# Versie_3.net
KiCad netlist of a schematic drawn in EAGLE
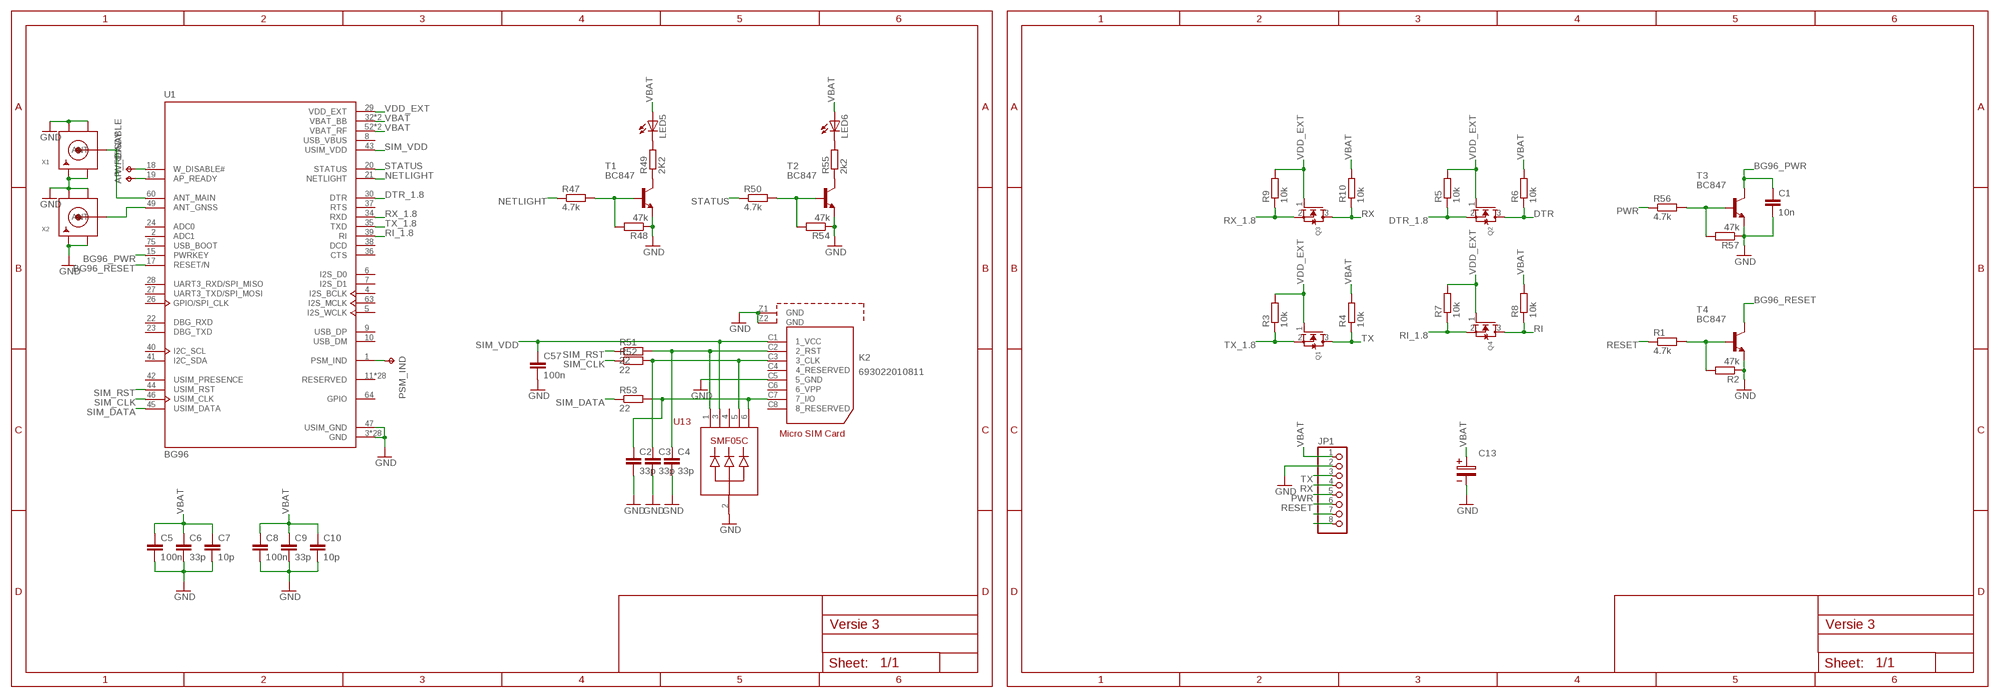
[diagram p0: schematic, sheet 1]

(export (version "E")
  (design (tool "Eeschema 10.0.6"))
  (components
    (comp (ref "AP_READY")
      (value "TPTP10R")
      (footprint "eagle-import:TP10R")
      (libsource (lib "eagle-import") (part "TPTP10R"))
    )
    (comp (ref "C1")
      (value "10n")
      (footprint "eagle-import:C0603")
      (libsource (lib "eagle-import") (part "C-EUC0603"))
    )
    (comp (ref "C2")
      (value "33p")
      (footprint "eagle-import:C0603")
      (libsource (lib "eagle-import") (part "C-EUC0603"))
    )
    (comp (ref "C3")
      (value "33p")
      (footprint "eagle-import:C0603")
      (libsource (lib "eagle-import") (part "C-EUC0603"))
    )
    (comp (ref "C4")
      (value "33p")
      (footprint "eagle-import:C0603")
      (libsource (lib "eagle-import") (part "C-EUC0603"))
    )
    (comp (ref "C5")
      (value "100n")
      (footprint "eagle-import:C0603")
      (libsource (lib "eagle-import") (part "C-EUC0603"))
    )
    (comp (ref "C6")
      (value "33p")
      (footprint "eagle-import:C0603")
      (libsource (lib "eagle-import") (part "C-EUC0603"))
    )
    (comp (ref "C7")
      (value "10p")
      (footprint "eagle-import:C0603")
      (libsource (lib "eagle-import") (part "C-EUC0603"))
    )
    (comp (ref "C8")
      (value "100n")
      (footprint "eagle-import:C0603")
      (libsource (lib "eagle-import") (part "C-EUC0603"))
    )
    (comp (ref "C9")
      (value "33p")
      (footprint "eagle-import:C0603")
      (libsource (lib "eagle-import") (part "C-EUC0603"))
    )
    (comp (ref "C10")
      (value "10p")
      (footprint "eagle-import:C0603")
      (libsource (lib "eagle-import") (part "C-EUC0603"))
    )
    (comp (ref "C13")
      (value "WCAP-ASLI_6,3X7,7_865080545012")
      (footprint "eagle-import:3.5X1.6X2.1(BXCXA)")
      (libsource (lib "eagle-import") (part "WCAP-ASLI_865080545012_6,3X7,7"))
    )
    (comp (ref "C57")
      (value "100n")
      (footprint "eagle-import:C0603")
      (libsource (lib "eagle-import") (part "C-EUC0603"))
    )
    (comp (ref "JP1")
      (value "PINHD-1X8")
      (footprint "eagle-import:1X08")
      (libsource (lib "eagle-import") (part "PINHD-1X8"))
    )
    (comp (ref "K2")
      (value "693022010811")
      (footprint "eagle-import:693022010811")
      (libsource (lib "eagle-import") (part "693022010811"))
    )
    (comp (ref "LED5")
      (value "LEDCHIPLED_0805")
      (footprint "eagle-import:CHIPLED_0805")
      (libsource (lib "eagle-import") (part "LEDCHIPLED_0805"))
    )
    (comp (ref "LED6")
      (value "LEDCHIPLED_0805")
      (footprint "eagle-import:CHIPLED_0805")
      (libsource (lib "eagle-import") (part "LEDCHIPLED_0805"))
    )
    (comp (ref "PSM_IND")
      (value "TPTP10R")
      (footprint "eagle-import:TP10R")
      (libsource (lib "eagle-import") (part "TPTP10R"))
    )
    (comp (ref "Q1")
      (value "MOSFET-NREFLOW")
      (footprint "eagle-import:SOT23")
      (libsource (lib "eagle-import") (part "MOSFET-NREFLOW"))
    )
    (comp (ref "Q2")
      (value "MOSFET-NREFLOW")
      (footprint "eagle-import:SOT23")
      (libsource (lib "eagle-import") (part "MOSFET-NREFLOW"))
    )
    (comp (ref "Q3")
      (value "MOSFET-NREFLOW")
      (footprint "eagle-import:SOT23")
      (libsource (lib "eagle-import") (part "MOSFET-NREFLOW"))
    )
    (comp (ref "Q4")
      (value "MOSFET-NREFLOW")
      (footprint "eagle-import:SOT23")
      (libsource (lib "eagle-import") (part "MOSFET-NREFLOW"))
    )
    (comp (ref "R1")
      (value "4.7k")
      (footprint "eagle-import:R0603")
      (libsource (lib "eagle-import") (part "R-EU_R0603"))
    )
    (comp (ref "R2")
      (value "47k")
      (footprint "eagle-import:R0603")
      (libsource (lib "eagle-import") (part "R-EU_R0603"))
    )
    (comp (ref "R3")
      (value "10k")
      (footprint "eagle-import:R0603")
      (libsource (lib "eagle-import") (part "R-EU_R0603"))
    )
    (comp (ref "R4")
      (value "10k")
      (footprint "eagle-import:R0603")
      (libsource (lib "eagle-import") (part "R-EU_R0603"))
    )
    (comp (ref "R5")
      (value "10k")
      (footprint "eagle-import:R0603")
      (libsource (lib "eagle-import") (part "R-EU_R0603"))
    )
    (comp (ref "R6")
      (value "10k")
      (footprint "eagle-import:R0603")
      (libsource (lib "eagle-import") (part "R-EU_R0603"))
    )
    (comp (ref "R7")
      (value "10k")
      (footprint "eagle-import:R0603")
      (libsource (lib "eagle-import") (part "R-EU_R0603"))
    )
    (comp (ref "R8")
      (value "10k")
      (footprint "eagle-import:R0603")
      (libsource (lib "eagle-import") (part "R-EU_R0603"))
    )
    (comp (ref "R9")
      (value "10k")
      (footprint "eagle-import:R0603")
      (libsource (lib "eagle-import") (part "R-EU_R0603"))
    )
    (comp (ref "R10")
      (value "10k")
      (footprint "eagle-import:R0603")
      (libsource (lib "eagle-import") (part "R-EU_R0603"))
    )
    (comp (ref "R47")
      (value "4.7k")
      (footprint "eagle-import:R0603")
      (libsource (lib "eagle-import") (part "R-EU_R0603"))
    )
    (comp (ref "R48")
      (value "47k")
      (footprint "eagle-import:R0603")
      (libsource (lib "eagle-import") (part "R-EU_R0603"))
    )
    (comp (ref "R49")
      (value "2K2")
      (footprint "eagle-import:R0603")
      (libsource (lib "eagle-import") (part "R-EU_R0603"))
    )
    (comp (ref "R50")
      (value "4.7k")
      (footprint "eagle-import:R0603")
      (libsource (lib "eagle-import") (part "R-EU_R0603"))
    )
    (comp (ref "R51")
      (value "22")
      (footprint "eagle-import:R0603")
      (libsource (lib "eagle-import") (part "R-EU_R0603"))
    )
    (comp (ref "R52")
      (value "22")
      (footprint "eagle-import:R0603")
      (libsource (lib "eagle-import") (part "R-EU_R0603"))
    )
    (comp (ref "R53")
      (value "22")
      (footprint "eagle-import:R0603")
      (libsource (lib "eagle-import") (part "R-EU_R0603"))
    )
    (comp (ref "R54")
      (value "47k")
      (footprint "eagle-import:R0603")
      (libsource (lib "eagle-import") (part "R-EU_R0603"))
    )
    (comp (ref "R55")
      (value "2k2")
      (footprint "eagle-import:R0603")
      (libsource (lib "eagle-import") (part "R-EU_R0603"))
    )
    (comp (ref "R56")
      (value "4.7k")
      (footprint "eagle-import:R0603")
      (libsource (lib "eagle-import") (part "R-EU_R0603"))
    )
    (comp (ref "R57")
      (value "47k")
      (footprint "eagle-import:R0603")
      (libsource (lib "eagle-import") (part "R-EU_R0603"))
    )
    (comp (ref "T1")
      (value "BC847")
      (footprint "eagle-import:SOT23")
      (libsource (lib "eagle-import") (part "BC847"))
    )
    (comp (ref "T2")
      (value "BC847")
      (footprint "eagle-import:SOT23")
      (libsource (lib "eagle-import") (part "BC847"))
    )
    (comp (ref "T3")
      (value "BC847")
      (footprint "eagle-import:SOT23")
      (libsource (lib "eagle-import") (part "BC847"))
    )
    (comp (ref "T4")
      (value "BC847")
      (footprint "eagle-import:SOT23")
      (libsource (lib "eagle-import") (part "BC847"))
    )
    (comp (ref "U1")
      (value "BG96")
      (footprint "eagle-import:LTE_MODULE_BG96")
      (fields (field (name "MF") "Quectel"))
      (libsource (lib "eagle-import") (part "BG96"))
    )
    (comp (ref "U13")
      (value "SMF05C")
      (footprint "eagle-import:SC-70-6")
      (libsource (lib "eagle-import") (part "SMF05C"))
    )
    (comp (ref "W_DISABLE")
      (value "TPTP10R")
      (footprint "eagle-import:TP10R")
      (libsource (lib "eagle-import") (part "TPTP10R"))
    )
    (comp (ref "X1")
      (value "SMACONNECTOR_EDGE_UFL")
      (footprint "eagle-import:SMA_EDGELAUNCH_UFL")
      (libsource (lib "eagle-import") (part "SMACONNECTOR_EDGE_UFL"))
    )
    (comp (ref "X2")
      (value "SMACONNECTOR_EDGE_UFL")
      (footprint "eagle-import:SMA_EDGELAUNCH_UFL")
      (libsource (lib "eagle-import") (part "SMACONNECTOR_EDGE_UFL"))
    )
  )
  (nets
    (net (code "1") (name "/BG96_PWR") (class "Default")
      (node (ref "C1") (pin "1") (pinfunction "1_1") (pintype "passive"))
      (node (ref "T3") (pin "3") (pinfunction "C_3") (pintype "passive"))
      (node (ref "U1") (pin "15") (pinfunction "PWRKEY_15") (pintype "input"))
    )
    (net (code "2") (name "/BG96_RESET") (class "Default")
      (node (ref "T4") (pin "3") (pinfunction "C_3") (pintype "passive"))
      (node (ref "U1") (pin "17") (pinfunction "RESET/N_17") (pintype "input"))
    )
    (net (code "3") (name "/DTR") (class "Default")
      (node (ref "JP1") (pin "7") (pinfunction "7_7") (pintype "passive"))
      (node (ref "Q2") (pin "3") (pinfunction "D_3") (pintype "bidirectional"))
      (node (ref "R6") (pin "1") (pinfunction "1_1") (pintype "passive"))
    )
    (net (code "4") (name "/DTR_1.8") (class "Default")
      (node (ref "Q2") (pin "2") (pinfunction "S_2") (pintype "bidirectional"))
      (node (ref "R5") (pin "1") (pinfunction "1_1") (pintype "passive"))
      (node (ref "U1") (pin "30") (pinfunction "DTR_30") (pintype "input"))
    )
    (net (code "5") (name "/NETLIGHT") (class "Default")
      (node (ref "R47") (pin "1") (pinfunction "1_1") (pintype "passive"))
      (node (ref "U1") (pin "21") (pinfunction "NETLIGHT_21") (pintype "output"))
    )
    (net (code "6") (name "/PWR") (class "Default")
      (node (ref "JP1") (pin "5") (pinfunction "5_5") (pintype "passive"))
      (node (ref "R56") (pin "1") (pinfunction "1_1") (pintype "passive"))
    )
    (net (code "7") (name "/RESET") (class "Default")
      (node (ref "JP1") (pin "6") (pinfunction "6_6") (pintype "passive"))
      (node (ref "R1") (pin "1") (pinfunction "1_1") (pintype "passive"))
    )
    (net (code "8") (name "/RI") (class "Default")
      (node (ref "JP1") (pin "8") (pinfunction "8_8") (pintype "passive"))
      (node (ref "Q4") (pin "3") (pinfunction "D_3") (pintype "bidirectional"))
      (node (ref "R8") (pin "1") (pinfunction "1_1") (pintype "passive"))
    )
    (net (code "9") (name "/RI_1.8") (class "Default")
      (node (ref "Q4") (pin "2") (pinfunction "S_2") (pintype "bidirectional"))
      (node (ref "R7") (pin "1") (pinfunction "1_1") (pintype "passive"))
      (node (ref "U1") (pin "39") (pinfunction "RI_39") (pintype "output"))
    )
    (net (code "10") (name "/RX") (class "Default")
      (node (ref "JP1") (pin "4") (pinfunction "4_4") (pintype "passive"))
      (node (ref "Q3") (pin "3") (pinfunction "D_3") (pintype "bidirectional"))
      (node (ref "R10") (pin "1") (pinfunction "1_1") (pintype "passive"))
    )
    (net (code "11") (name "/RX_1.8") (class "Default")
      (node (ref "Q3") (pin "2") (pinfunction "S_2") (pintype "bidirectional"))
      (node (ref "R9") (pin "1") (pinfunction "1_1") (pintype "passive"))
      (node (ref "U1") (pin "34") (pinfunction "RXD_34") (pintype "input"))
    )
    (net (code "12") (name "/SIM_CLK") (class "Default")
      (node (ref "R52") (pin "1") (pinfunction "1_1") (pintype "passive"))
      (node (ref "U1") (pin "46") (pinfunction "USIM_CLK_46") (pintype "output"))
    )
    (net (code "13") (name "/SIM_DATA") (class "Default")
      (node (ref "R53") (pin "1") (pinfunction "1_1") (pintype "passive"))
      (node (ref "U1") (pin "45") (pinfunction "USIM_DATA_45") (pintype "bidirectional"))
    )
    (net (code "14") (name "/SIM_RST") (class "Default")
      (node (ref "R51") (pin "1") (pinfunction "1_1") (pintype "passive"))
      (node (ref "U1") (pin "44") (pinfunction "USIM_RST_44") (pintype "output"))
    )
    (net (code "15") (name "/SIM_VDD") (class "Default")
      (node (ref "C57") (pin "1") (pinfunction "1_1") (pintype "passive"))
      (node (ref "K2") (pin "C1") (pinfunction "1_VCC_C1") (pintype "bidirectional"))
      (node (ref "U1") (pin "43") (pinfunction "USIM_VDD_43") (pintype "power_in"))
      (node (ref "U13") (pin "3") (pinfunction "3_3") (pintype "bidirectional"))
    )
    (net (code "16") (name "/STATUS") (class "Default")
      (node (ref "R50") (pin "1") (pinfunction "1_1") (pintype "passive"))
      (node (ref "U1") (pin "20") (pinfunction "STATUS_20") (pintype "output"))
    )
    (net (code "17") (name "/TX") (class "Default")
      (node (ref "JP1") (pin "3") (pinfunction "3_3") (pintype "passive"))
      (node (ref "Q1") (pin "3") (pinfunction "D_3") (pintype "bidirectional"))
      (node (ref "R4") (pin "1") (pinfunction "1_1") (pintype "passive"))
    )
    (net (code "18") (name "/TX_1.8") (class "Default")
      (node (ref "Q1") (pin "2") (pinfunction "S_2") (pintype "bidirectional"))
      (node (ref "R3") (pin "1") (pinfunction "1_1") (pintype "passive"))
      (node (ref "U1") (pin "35") (pinfunction "TXD_35") (pintype "output"))
    )
    (net (code "19") (name "/USB_VBUS") (class "Default")
      (node (ref "U1") (pin "8") (pinfunction "USB_VBUS_8") (pintype "power_in"))
    )
    (net (code "20") (name "/VBAT") (class "Default")
      (node (ref "C10") (pin "1") (pinfunction "1_1") (pintype "passive"))
      (node (ref "C13") (pin "1") (pinfunction "1_1") (pintype "passive"))
      (node (ref "C5") (pin "1") (pinfunction "1_1") (pintype "passive"))
      (node (ref "C6") (pin "1") (pinfunction "1_1") (pintype "passive"))
      (node (ref "C7") (pin "1") (pinfunction "1_1") (pintype "passive"))
      (node (ref "C8") (pin "1") (pinfunction "1_1") (pintype "passive"))
      (node (ref "C9") (pin "1") (pinfunction "1_1") (pintype "passive"))
      (node (ref "JP1") (pin "1") (pinfunction "1_1") (pintype "passive"))
      (node (ref "LED5") (pin "A") (pinfunction "A_A") (pintype "passive"))
      (node (ref "LED6") (pin "A") (pinfunction "A_A") (pintype "passive"))
      (node (ref "R10") (pin "2") (pinfunction "2_2") (pintype "passive"))
      (node (ref "R4") (pin "2") (pinfunction "2_2") (pintype "passive"))
      (node (ref "R6") (pin "2") (pinfunction "2_2") (pintype "passive"))
      (node (ref "R8") (pin "2") (pinfunction "2_2") (pintype "passive"))
      (node (ref "U1") (pin "32") (pinfunction "VBAT_BB_32") (pintype "power_in"))
      (node (ref "U1") (pin "33") (pinfunction "VBAT_BB_33") (pintype "power_in"))
      (node (ref "U1") (pin "52") (pinfunction "VBAT_RF_52") (pintype "power_in"))
      (node (ref "U1") (pin "53") (pinfunction "VBAT_RF_53") (pintype "power_in"))
    )
    (net (code "21") (name "/VDD_EXT") (class "Default")
      (node (ref "Q1") (pin "1") (pinfunction "G_1") (pintype "bidirectional"))
      (node (ref "Q2") (pin "1") (pinfunction "G_1") (pintype "bidirectional"))
      (node (ref "Q3") (pin "1") (pinfunction "G_1") (pintype "bidirectional"))
      (node (ref "Q4") (pin "1") (pinfunction "G_1") (pintype "bidirectional"))
      (node (ref "R3") (pin "2") (pinfunction "2_2") (pintype "passive"))
      (node (ref "R5") (pin "2") (pinfunction "2_2") (pintype "passive"))
      (node (ref "R7") (pin "2") (pinfunction "2_2") (pintype "passive"))
      (node (ref "R9") (pin "2") (pinfunction "2_2") (pintype "passive"))
      (node (ref "U1") (pin "29") (pinfunction "VDD_EXT_29") (pintype "power_in"))
    )
    (net (code "22") (name "GND") (class "Default")
      (node (ref "C1") (pin "2") (pinfunction "2_2") (pintype "passive"))
      (node (ref "C10") (pin "2") (pinfunction "2_2") (pintype "passive"))
      (node (ref "C13") (pin "2") (pinfunction "2_2") (pintype "passive"))
      (node (ref "C2") (pin "2") (pinfunction "2_2") (pintype "passive"))
      (node (ref "C3") (pin "2") (pinfunction "2_2") (pintype "passive"))
      (node (ref "C4") (pin "2") (pinfunction "2_2") (pintype "passive"))
      (node (ref "C5") (pin "2") (pinfunction "2_2") (pintype "passive"))
      (node (ref "C57") (pin "2") (pinfunction "2_2") (pintype "passive"))
      (node (ref "C6") (pin "2") (pinfunction "2_2") (pintype "passive"))
      (node (ref "C7") (pin "2") (pinfunction "2_2") (pintype "passive"))
      (node (ref "C8") (pin "2") (pinfunction "2_2") (pintype "passive"))
      (node (ref "C9") (pin "2") (pinfunction "2_2") (pintype "passive"))
      (node (ref "JP1") (pin "2") (pinfunction "2_2") (pintype "passive"))
      (node (ref "K2") (pin "C5") (pinfunction "5_GND_C5") (pintype "bidirectional"))
      (node (ref "K2") (pin "Z1") (pinfunction "GND_Z1") (pintype "bidirectional"))
      (node (ref "K2") (pin "Z2") (pinfunction "GND_Z2") (pintype "bidirectional"))
      (node (ref "R2") (pin "1") (pinfunction "1_1") (pintype "passive"))
      (node (ref "R48") (pin "1") (pinfunction "1_1") (pintype "passive"))
      (node (ref "R54") (pin "1") (pinfunction "1_1") (pintype "passive"))
      (node (ref "R57") (pin "1") (pinfunction "1_1") (pintype "passive"))
      (node (ref "T1") (pin "2") (pinfunction "E_2") (pintype "passive"))
      (node (ref "T2") (pin "2") (pinfunction "E_2") (pintype "passive"))
      (node (ref "T3") (pin "2") (pinfunction "E_2") (pintype "passive"))
      (node (ref "T4") (pin "2") (pinfunction "E_2") (pintype "passive"))
      (node (ref "U1") (pin "100") (pinfunction "GND_100") (pintype "power_in"))
      (node (ref "U1") (pin "101") (pinfunction "GND_101") (pintype "power_in"))
      (node (ref "U1") (pin "102") (pinfunction "GND_102") (pintype "power_in"))
      (node (ref "U1") (pin "3") (pinfunction "GND_3") (pintype "power_in"))
      (node (ref "U1") (pin "31") (pinfunction "GND_31") (pintype "power_in"))
      (node (ref "U1") (pin "47") (pinfunction "USIM_GND_47") (pintype "power_in"))
      (node (ref "U1") (pin "48") (pinfunction "GND_48") (pintype "power_in"))
      (node (ref "U1") (pin "50") (pinfunction "GND_50") (pintype "power_in"))
      (node (ref "U1") (pin "54") (pinfunction "GND_54") (pintype "power_in"))
      (node (ref "U1") (pin "55") (pinfunction "GND_55") (pintype "power_in"))
      (node (ref "U1") (pin "58") (pinfunction "GND_58") (pintype "power_in"))
      (node (ref "U1") (pin "59") (pinfunction "GND_59") (pintype "power_in"))
      (node (ref "U1") (pin "61") (pinfunction "GND_61") (pintype "power_in"))
      (node (ref "U1") (pin "62") (pinfunction "GND_62") (pintype "power_in"))
      (node (ref "U1") (pin "67") (pinfunction "GND_67") (pintype "power_in"))
      (node (ref "U1") (pin "68") (pinfunction "GND_68") (pintype "power_in"))
      (node (ref "U1") (pin "69") (pinfunction "GND_69") (pintype "power_in"))
      (node (ref "U1") (pin "70") (pinfunction "GND_70") (pintype "power_in"))
      (node (ref "U1") (pin "71") (pinfunction "GND_71") (pintype "power_in"))
      (node (ref "U1") (pin "72") (pinfunction "GND_72") (pintype "power_in"))
      (node (ref "U1") (pin "73") (pinfunction "GND_73") (pintype "power_in"))
      (node (ref "U1") (pin "74") (pinfunction "GND_74") (pintype "power_in"))
      (node (ref "U1") (pin "79") (pinfunction "GND_79") (pintype "power_in"))
      (node (ref "U1") (pin "80") (pinfunction "GND_80") (pintype "power_in"))
      (node (ref "U1") (pin "81") (pinfunction "GND_81") (pintype "power_in"))
      (node (ref "U1") (pin "82") (pinfunction "GND_82") (pintype "power_in"))
      (node (ref "U1") (pin "89") (pinfunction "GND_89") (pintype "power_in"))
      (node (ref "U1") (pin "90") (pinfunction "GND_90") (pintype "power_in"))
      (node (ref "U1") (pin "91") (pinfunction "GND_91") (pintype "power_in"))
      (node (ref "U13") (pin "2") (pinfunction "2_2") (pintype "bidirectional"))
      (node (ref "X1") (pin "GND@1") (pinfunction "GND1_GND@1") (pintype "power_in"))
      (node (ref "X1") (pin "GND@2") (pinfunction "GND2_GND@2") (pintype "power_in"))
      (node (ref "X1") (pin "GND@3") (pinfunction "GND3_GND@3") (pintype "power_in"))
      (node (ref "X1") (pin "GND@4") (pinfunction "GND4_GND@4") (pintype "power_in"))
      (node (ref "X2") (pin "GND@1") (pinfunction "GND1_GND@1") (pintype "power_in"))
      (node (ref "X2") (pin "GND@2") (pinfunction "GND2_GND@2") (pintype "power_in"))
      (node (ref "X2") (pin "GND@3") (pinfunction "GND3_GND@3") (pintype "power_in"))
      (node (ref "X2") (pin "GND@4") (pinfunction "GND4_GND@4") (pintype "power_in"))
    )
    (net (code "23") (name "Net-(K2-2_RST)") (class "Default")
      (node (ref "C4") (pin "1") (pinfunction "1_1") (pintype "passive"))
      (node (ref "K2") (pin "C2") (pinfunction "2_RST_C2") (pintype "bidirectional"))
      (node (ref "R51") (pin "2") (pinfunction "2_2") (pintype "passive"))
      (node (ref "U13") (pin "1") (pinfunction "1_1") (pintype "bidirectional"))
    )
    (net (code "24") (name "Net-(K2-3_CLK)") (class "Default")
      (node (ref "C3") (pin "1") (pinfunction "1_1") (pintype "passive"))
      (node (ref "K2") (pin "C3") (pinfunction "3_CLK_C3") (pintype "bidirectional"))
      (node (ref "R52") (pin "2") (pinfunction "2_2") (pintype "passive"))
      (node (ref "U13") (pin "5") (pinfunction "5_5") (pintype "bidirectional"))
    )
    (net (code "25") (name "Net-(K2-7_I{slash}O)") (class "Default")
      (node (ref "C2") (pin "1") (pinfunction "1_1") (pintype "passive"))
      (node (ref "K2") (pin "C7") (pinfunction "7_I/O_C7") (pintype "bidirectional"))
      (node (ref "R53") (pin "2") (pinfunction "2_2") (pintype "passive"))
      (node (ref "U13") (pin "6") (pinfunction "6_6") (pintype "bidirectional"))
    )
    (net (code "26") (name "Net-(LED5-PadC)") (class "Default")
      (node (ref "LED5") (pin "C") (pinfunction "C_C") (pintype "passive"))
      (node (ref "R49") (pin "2") (pinfunction "2_2") (pintype "passive"))
    )
    (net (code "27") (name "Net-(LED6-PadC)") (class "Default")
      (node (ref "LED6") (pin "C") (pinfunction "C_C") (pintype "passive"))
      (node (ref "R55") (pin "2") (pinfunction "2_2") (pintype "passive"))
    )
    (net (code "28") (name "Net-(T1-B)") (class "Default")
      (node (ref "R47") (pin "2") (pinfunction "2_2") (pintype "passive"))
      (node (ref "R48") (pin "2") (pinfunction "2_2") (pintype "passive"))
      (node (ref "T1") (pin "1") (pinfunction "B_1") (pintype "passive"))
    )
    (net (code "29") (name "Net-(T1-C)") (class "Default")
      (node (ref "R49") (pin "1") (pinfunction "1_1") (pintype "passive"))
      (node (ref "T1") (pin "3") (pinfunction "C_3") (pintype "passive"))
    )
    (net (code "30") (name "Net-(T2-B)") (class "Default")
      (node (ref "R50") (pin "2") (pinfunction "2_2") (pintype "passive"))
      (node (ref "R54") (pin "2") (pinfunction "2_2") (pintype "passive"))
      (node (ref "T2") (pin "1") (pinfunction "B_1") (pintype "passive"))
    )
    (net (code "31") (name "Net-(T2-C)") (class "Default")
      (node (ref "R55") (pin "1") (pinfunction "1_1") (pintype "passive"))
      (node (ref "T2") (pin "3") (pinfunction "C_3") (pintype "passive"))
    )
    (net (code "32") (name "Net-(T3-B)") (class "Default")
      (node (ref "R56") (pin "2") (pinfunction "2_2") (pintype "passive"))
      (node (ref "R57") (pin "2") (pinfunction "2_2") (pintype "passive"))
      (node (ref "T3") (pin "1") (pinfunction "B_1") (pintype "passive"))
    )
    (net (code "33") (name "Net-(T4-B)") (class "Default")
      (node (ref "R1") (pin "2") (pinfunction "2_2") (pintype "passive"))
      (node (ref "R2") (pin "2") (pinfunction "2_2") (pintype "passive"))
      (node (ref "T4") (pin "1") (pinfunction "B_1") (pintype "passive"))
    )
    (net (code "34") (name "Net-(U1-ANT_GNSS)") (class "Default")
      (node (ref "U1") (pin "49") (pinfunction "ANT_GNSS_49") (pintype "input"))
      (node (ref "X2") (pin "P") (pinfunction "ANT_P") (pintype "bidirectional"))
    )
    (net (code "35") (name "Net-(U1-ANT_MAIN)") (class "Default")
      (node (ref "U1") (pin "60") (pinfunction "ANT_MAIN_60") (pintype "bidirectional"))
      (node (ref "X1") (pin "P") (pinfunction "ANT_P") (pintype "bidirectional"))
    )
    (net (code "36") (name "Net-(U1-AP_READY)") (class "Default")
      (node (ref "AP_READY") (pin "TP") (pinfunction "TP_TP") (pintype "input"))
      (node (ref "U1") (pin "19") (pinfunction "AP_READY_19") (pintype "input"))
    )
    (net (code "37") (name "Net-(U1-PSM_IND)") (class "Default")
      (node (ref "PSM_IND") (pin "TP") (pinfunction "TP_TP") (pintype "input"))
      (node (ref "U1") (pin "1") (pinfunction "PSM_IND_1") (pintype "output"))
    )
    (net (code "38") (name "Net-(U1-W_DISABLE#)") (class "Default")
      (node (ref "U1") (pin "18") (pinfunction "W_DISABLE#_18") (pintype "input"))
      (node (ref "W_DISABLE") (pin "TP") (pinfunction "TP_TP") (pintype "input"))
    )
    (net (code "39") (name "unconnected-(K2-4_RESERVED-PadC4)") (class "Default")
      (node (ref "K2") (pin "C4") (pinfunction "4_RESERVED_C4") (pintype "bidirectional"))
    )
    (net (code "40") (name "unconnected-(K2-6_VPP-PadC6)") (class "Default")
      (node (ref "K2") (pin "C6") (pinfunction "6_VPP_C6") (pintype "bidirectional"))
    )
    (net (code "41") (name "unconnected-(K2-8_RESERVED-PadC8)") (class "Default")
      (node (ref "K2") (pin "C8") (pinfunction "8_RESERVED_C8") (pintype "bidirectional"))
    )
    (net (code "42") (name "unconnected-(U1-ADC0-Pad24)") (class "Default")
      (node (ref "U1") (pin "24") (pinfunction "ADC0_24") (pintype "input"))
    )
    (net (code "43") (name "unconnected-(U1-ADC1-Pad2)") (class "Default")
      (node (ref "U1") (pin "2") (pinfunction "ADC1_2") (pintype "input"))
    )
    (net (code "44") (name "unconnected-(U1-CTS-Pad36)") (class "Default")
      (node (ref "U1") (pin "36") (pinfunction "CTS_36") (pintype "output"))
    )
    (net (code "45") (name "unconnected-(U1-DBG_RXD-Pad22)") (class "Default")
      (node (ref "U1") (pin "22") (pinfunction "DBG_RXD_22") (pintype "input"))
    )
    (net (code "46") (name "unconnected-(U1-DBG_TXD-Pad23)") (class "Default")
      (node (ref "U1") (pin "23") (pinfunction "DBG_TXD_23") (pintype "output"))
    )
    (net (code "47") (name "unconnected-(U1-DCD-Pad38)") (class "Default")
      (node (ref "U1") (pin "38") (pinfunction "DCD_38") (pintype "output"))
    )
    (net (code "48") (name "unconnected-(U1-GPIO-Pad64)") (class "Default")
      (node (ref "U1") (pin "64") (pinfunction "GPIO_64") (pintype "bidirectional"))
    )
    (net (code "49") (name "unconnected-(U1-GPIO{slash}SPI_CLK-Pad26)") (class "Default")
      (node (ref "U1") (pin "26") (pinfunction "GPIO/SPI_CLK_26") (pintype "output"))
    )
    (net (code "50") (name "unconnected-(U1-I2C_SCL-Pad40)") (class "Default")
      (node (ref "U1") (pin "40") (pinfunction "I2C_SCL_40") (pintype "input"))
    )
    (net (code "51") (name "unconnected-(U1-I2C_SDA-Pad41)") (class "Default")
      (node (ref "U1") (pin "41") (pinfunction "I2C_SDA_41") (pintype "bidirectional"))
    )
    (net (code "52") (name "unconnected-(U1-I2S_BCLK-Pad4)") (class "Default")
      (node (ref "U1") (pin "4") (pinfunction "I2S_BCLK_4") (pintype "output"))
    )
    (net (code "53") (name "unconnected-(U1-I2S_D0-Pad6)") (class "Default")
      (node (ref "U1") (pin "6") (pinfunction "I2S_D0_6") (pintype "bidirectional"))
    )
    (net (code "54") (name "unconnected-(U1-I2S_D1-Pad7)") (class "Default")
      (node (ref "U1") (pin "7") (pinfunction "I2S_D1_7") (pintype "bidirectional"))
    )
    (net (code "55") (name "unconnected-(U1-I2S_MCLK-Pad63)") (class "Default")
      (node (ref "U1") (pin "63") (pinfunction "I2S_MCLK_63") (pintype "output"))
    )
    (net (code "56") (name "unconnected-(U1-I2S_WCLK-Pad5)") (class "Default")
      (node (ref "U1") (pin "5") (pinfunction "I2S_WCLK_5") (pintype "output"))
    )
    (net (code "57") (name "unconnected-(U1-RESERVED-Pad11)") (class "Default")
      (node (ref "U1") (pin "11") (pinfunction "RESERVED_11") (pintype "no_connect"))
    )
    (net (code "58") (name "unconnected-(U1-RESERVED-Pad12)") (class "Default")
      (node (ref "U1") (pin "12") (pinfunction "RESERVED_12") (pintype "no_connect"))
    )
    (net (code "59") (name "unconnected-(U1-RESERVED-Pad13)") (class "Default")
      (node (ref "U1") (pin "13") (pinfunction "RESERVED_13") (pintype "no_connect"))
    )
    (net (code "60") (name "unconnected-(U1-RESERVED-Pad14)") (class "Default")
      (node (ref "U1") (pin "14") (pinfunction "RESERVED_14") (pintype "no_connect"))
    )
    (net (code "61") (name "unconnected-(U1-RESERVED-Pad16)") (class "Default")
      (node (ref "U1") (pin "16") (pinfunction "RESERVED_16") (pintype "no_connect"))
    )
    (net (code "62") (name "unconnected-(U1-RESERVED-Pad25)") (class "Default")
      (node (ref "U1") (pin "25") (pinfunction "RESERVED_25") (pintype "no_connect"))
    )
    (net (code "63") (name "unconnected-(U1-RESERVED-Pad51)") (class "Default")
      (node (ref "U1") (pin "51") (pinfunction "RESERVED_51") (pintype "no_connect"))
    )
    (net (code "64") (name "unconnected-(U1-RESERVED-Pad56)") (class "Default")
      (node (ref "U1") (pin "56") (pinfunction "RESERVED_56") (pintype "no_connect"))
    )
    (net (code "65") (name "unconnected-(U1-RESERVED-Pad57)") (class "Default")
      (node (ref "U1") (pin "57") (pinfunction "RESERVED_57") (pintype "no_connect"))
    )
    (net (code "66") (name "unconnected-(U1-RESERVED-Pad65)") (class "Default")
      (node (ref "U1") (pin "65") (pinfunction "RESERVED_65") (pintype "no_connect"))
    )
    (net (code "67") (name "unconnected-(U1-RESERVED-Pad66)") (class "Default")
      (node (ref "U1") (pin "66") (pinfunction "RESERVED_66") (pintype "no_connect"))
    )
    (net (code "68") (name "unconnected-(U1-RESERVED-Pad76)") (class "Default")
      (node (ref "U1") (pin "76") (pinfunction "RESERVED_76") (pintype "no_connect"))
    )
    (net (code "69") (name "unconnected-(U1-RESERVED-Pad77)") (class "Default")
      (node (ref "U1") (pin "77") (pinfunction "RESERVED_77") (pintype "no_connect"))
    )
    (net (code "70") (name "unconnected-(U1-RESERVED-Pad78)") (class "Default")
      (node (ref "U1") (pin "78") (pinfunction "RESERVED_78") (pintype "no_connect"))
    )
    (net (code "71") (name "unconnected-(U1-RESERVED-Pad83)") (class "Default")
      (node (ref "U1") (pin "83") (pinfunction "RESERVED_83") (pintype "no_connect"))
    )
    (net (code "72") (name "unconnected-(U1-RESERVED-Pad84)") (class "Default")
      (node (ref "U1") (pin "84") (pinfunction "RESERVED_84") (pintype "no_connect"))
    )
    (net (code "73") (name "unconnected-(U1-RESERVED-Pad85)") (class "Default")
      (node (ref "U1") (pin "85") (pinfunction "RESERVED_85") (pintype "no_connect"))
    )
    (net (code "74") (name "unconnected-(U1-RESERVED-Pad86)") (class "Default")
      (node (ref "U1") (pin "86") (pinfunction "RESERVED_86") (pintype "no_connect"))
    )
    (net (code "75") (name "unconnected-(U1-RESERVED-Pad87)") (class "Default")
      (node (ref "U1") (pin "87") (pinfunction "RESERVED_87") (pintype "no_connect"))
    )
    (net (code "76") (name "unconnected-(U1-RESERVED-Pad88)") (class "Default")
      (node (ref "U1") (pin "88") (pinfunction "RESERVED_88") (pintype "no_connect"))
    )
    (net (code "77") (name "unconnected-(U1-RESERVED-Pad92)") (class "Default")
      (node (ref "U1") (pin "92") (pinfunction "RESERVED_92") (pintype "no_connect"))
    )
    (net (code "78") (name "unconnected-(U1-RESERVED-Pad93)") (class "Default")
      (node (ref "U1") (pin "93") (pinfunction "RESERVED_93") (pintype "no_connect"))
    )
    (net (code "79") (name "unconnected-(U1-RESERVED-Pad94)") (class "Default")
      (node (ref "U1") (pin "94") (pinfunction "RESERVED_94") (pintype "no_connect"))
    )
    (net (code "80") (name "unconnected-(U1-RESERVED-Pad95)") (class "Default")
      (node (ref "U1") (pin "95") (pinfunction "RESERVED_95") (pintype "no_connect"))
    )
    (net (code "81") (name "unconnected-(U1-RESERVED-Pad96)") (class "Default")
      (node (ref "U1") (pin "96") (pinfunction "RESERVED_96") (pintype "no_connect"))
    )
    (net (code "82") (name "unconnected-(U1-RESERVED-Pad97)") (class "Default")
      (node (ref "U1") (pin "97") (pinfunction "RESERVED_97") (pintype "no_connect"))
    )
    (net (code "83") (name "unconnected-(U1-RESERVED-Pad98)") (class "Default")
      (node (ref "U1") (pin "98") (pinfunction "RESERVED_98") (pintype "no_connect"))
    )
    (net (code "84") (name "unconnected-(U1-RESERVED-Pad99)") (class "Default")
      (node (ref "U1") (pin "99") (pinfunction "RESERVED_99") (pintype "no_connect"))
    )
    (net (code "85") (name "unconnected-(U1-RTS-Pad37)") (class "Default")
      (node (ref "U1") (pin "37") (pinfunction "RTS_37") (pintype "input"))
    )
    (net (code "86") (name "unconnected-(U1-UART3_RXD{slash}SPI_MISO-Pad28)") (class "Default")
      (node (ref "U1") (pin "28") (pinfunction "UART3_RXD/SPI_MISO_28") (pintype "input"))
    )
    (net (code "87") (name "unconnected-(U1-UART3_TXD{slash}SPI_MOSI-Pad27)") (class "Default")
      (node (ref "U1") (pin "27") (pinfunction "UART3_TXD/SPI_MOSI_27") (pintype "output"))
    )
    (net (code "88") (name "unconnected-(U1-USB_BOOT-Pad75)") (class "Default")
      (node (ref "U1") (pin "75") (pinfunction "USB_BOOT_75") (pintype "input"))
    )
    (net (code "89") (name "unconnected-(U1-USB_DM-Pad10)") (class "Default")
      (node (ref "U1") (pin "10") (pinfunction "USB_DM_10") (pintype "bidirectional"))
    )
    (net (code "90") (name "unconnected-(U1-USB_DP-Pad9)") (class "Default")
      (node (ref "U1") (pin "9") (pinfunction "USB_DP_9") (pintype "bidirectional"))
    )
    (net (code "91") (name "unconnected-(U1-USIM_PRESENCE-Pad42)") (class "Default")
      (node (ref "U1") (pin "42") (pinfunction "USIM_PRESENCE_42") (pintype "input"))
    )
    (net (code "92") (name "unconnected-(U13-Pad4)") (class "Default")
      (node (ref "U13") (pin "4") (pinfunction "4_4") (pintype "bidirectional"))
    )
  )
)
